# B172X.net
KiCad netlist of a schematic drawn in EAGLE
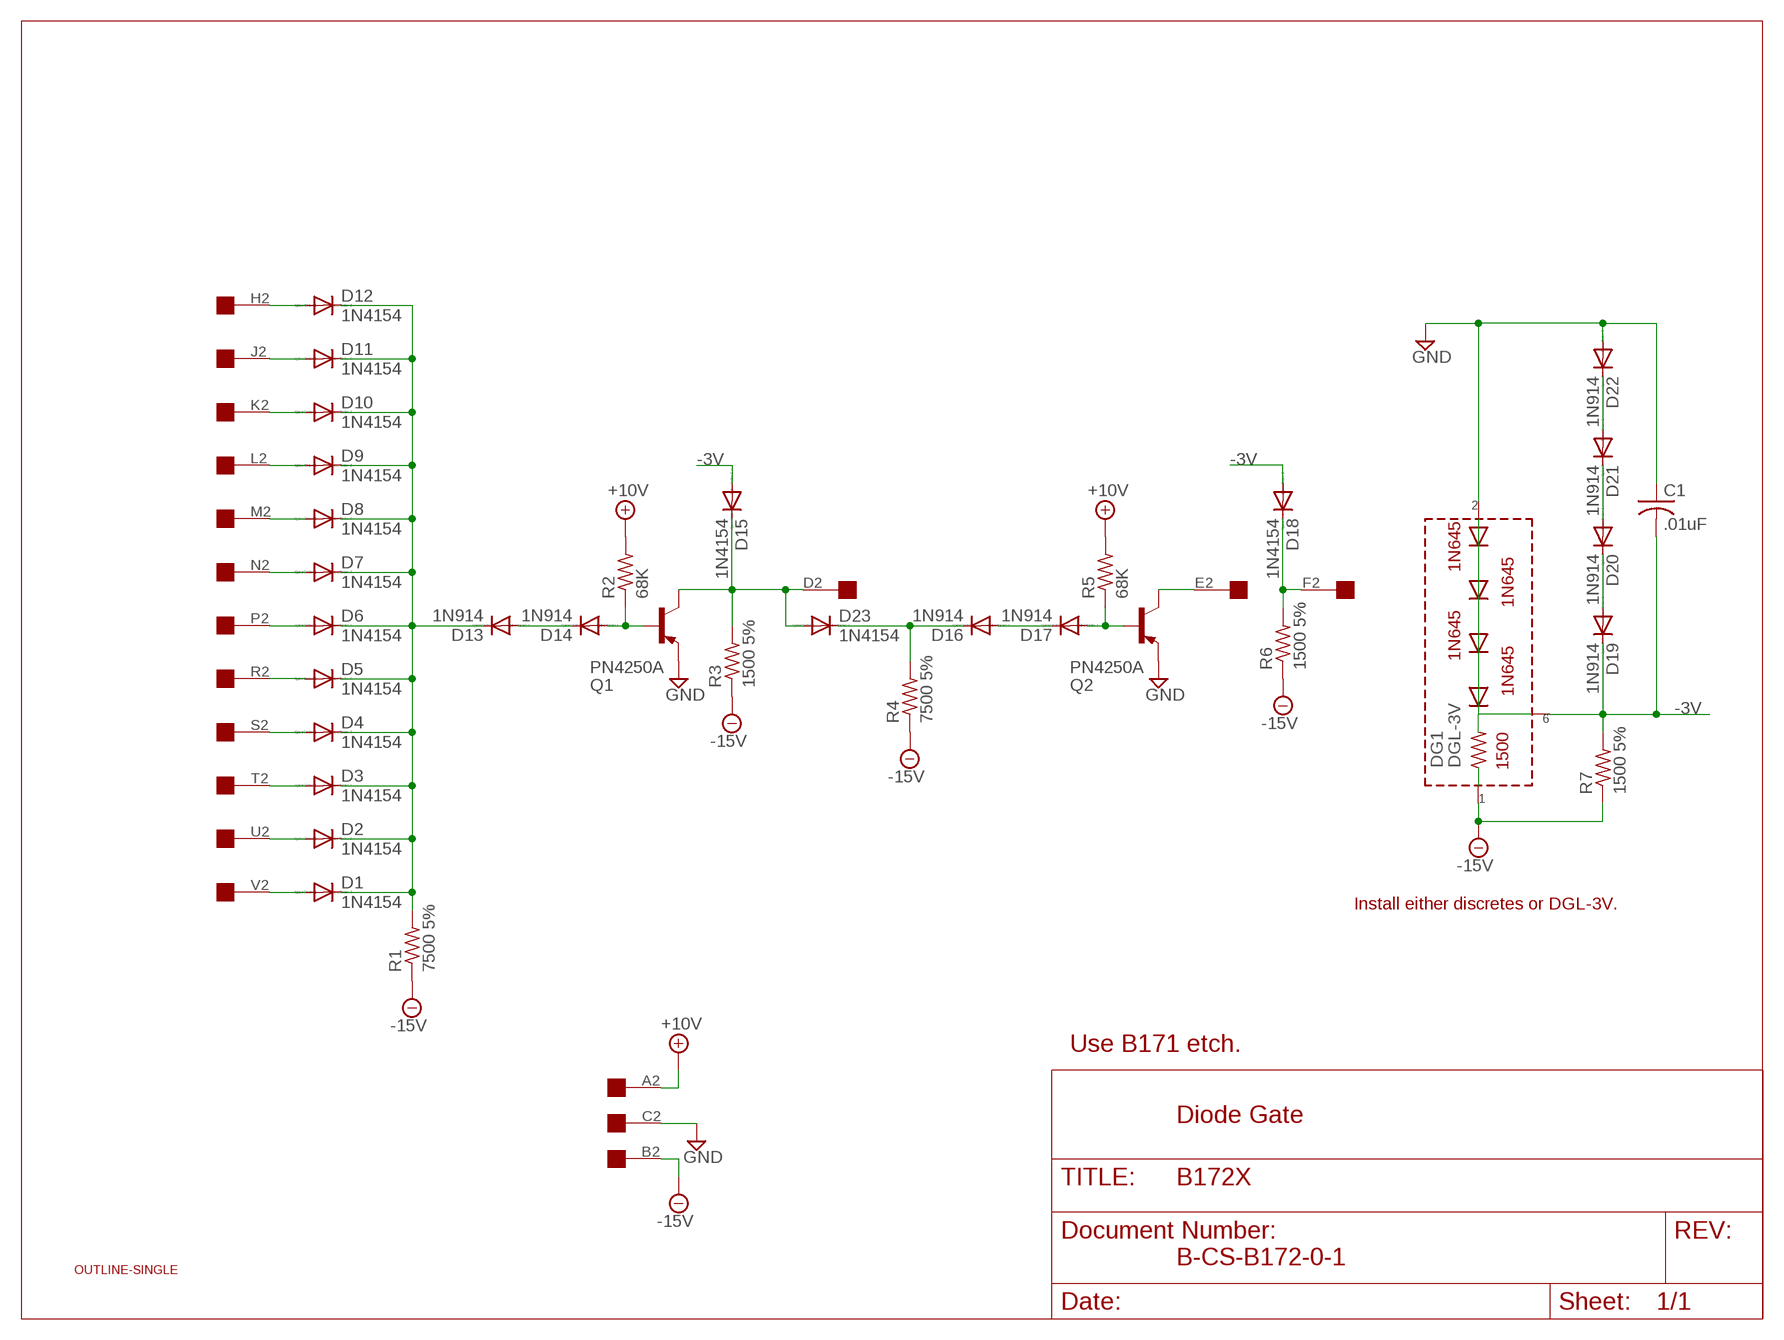
[diagram p0: schematic, sheet 1]

(export (version "E")
  (design (tool "Eeschema 10.0.6"))
  (components
    (comp (ref "C1")
      (value ".01uF")
      (footprint "eagle-import:C050-025X075")
      (libsource (lib "eagle-import") (part "C-US050-025X075"))
    )
    (comp (ref "D1")
      (value "1N4154")
      (footprint "eagle-import:DO35-10")
      (libsource (lib "eagle-import") (part "DIODE-DO35-10"))
    )
    (comp (ref "D2")
      (value "1N4154")
      (footprint "eagle-import:DO35-10")
      (libsource (lib "eagle-import") (part "DIODE-DO35-10"))
    )
    (comp (ref "D3")
      (value "1N4154")
      (footprint "eagle-import:DO35-10")
      (libsource (lib "eagle-import") (part "DIODE-DO35-10"))
    )
    (comp (ref "D4")
      (value "1N4154")
      (footprint "eagle-import:DO35-10")
      (libsource (lib "eagle-import") (part "DIODE-DO35-10"))
    )
    (comp (ref "D5")
      (value "1N4154")
      (footprint "eagle-import:DO35-10")
      (libsource (lib "eagle-import") (part "DIODE-DO35-10"))
    )
    (comp (ref "D6")
      (value "1N4154")
      (footprint "eagle-import:DO35-10")
      (libsource (lib "eagle-import") (part "DIODE-DO35-10"))
    )
    (comp (ref "D7")
      (value "1N4154")
      (footprint "eagle-import:DO35-10")
      (libsource (lib "eagle-import") (part "DIODE-DO35-10"))
    )
    (comp (ref "D8")
      (value "1N4154")
      (footprint "eagle-import:DO35-10")
      (libsource (lib "eagle-import") (part "DIODE-DO35-10"))
    )
    (comp (ref "D9")
      (value "1N4154")
      (footprint "eagle-import:DO35-10")
      (libsource (lib "eagle-import") (part "DIODE-DO35-10"))
    )
    (comp (ref "D10")
      (value "1N4154")
      (footprint "eagle-import:DO35-10")
      (libsource (lib "eagle-import") (part "DIODE-DO35-10"))
    )
    (comp (ref "D11")
      (value "1N4154")
      (footprint "eagle-import:DO35-10")
      (libsource (lib "eagle-import") (part "DIODE-DO35-10"))
    )
    (comp (ref "D12")
      (value "1N4154")
      (footprint "eagle-import:DO35-10")
      (libsource (lib "eagle-import") (part "DIODE-DO35-10"))
    )
    (comp (ref "D13")
      (value "1N914")
      (footprint "eagle-import:DO35-10")
      (libsource (lib "eagle-import") (part "DIODE-DO35-10"))
    )
    (comp (ref "D14")
      (value "1N914")
      (footprint "eagle-import:DO35-10")
      (libsource (lib "eagle-import") (part "DIODE-DO35-10"))
    )
    (comp (ref "D15")
      (value "1N4154")
      (footprint "eagle-import:DO35-10")
      (libsource (lib "eagle-import") (part "DIODE-DO35-10"))
    )
    (comp (ref "D16")
      (value "1N914")
      (footprint "eagle-import:DO35-10")
      (libsource (lib "eagle-import") (part "DIODE-DO35-10"))
    )
    (comp (ref "D17")
      (value "1N914")
      (footprint "eagle-import:DO35-10")
      (libsource (lib "eagle-import") (part "DIODE-DO35-10"))
    )
    (comp (ref "D18")
      (value "1N4154")
      (footprint "eagle-import:DO35-10")
      (libsource (lib "eagle-import") (part "DIODE-DO35-10"))
    )
    (comp (ref "D19")
      (value "1N914")
      (footprint "eagle-import:DO35-10")
      (libsource (lib "eagle-import") (part "DIODE-DO35-10"))
    )
    (comp (ref "D20")
      (value "1N914")
      (footprint "eagle-import:DO35-10")
      (libsource (lib "eagle-import") (part "DIODE-DO35-10"))
    )
    (comp (ref "D21")
      (value "1N914")
      (footprint "eagle-import:DO35-10")
      (libsource (lib "eagle-import") (part "DIODE-DO35-10"))
    )
    (comp (ref "D22")
      (value "1N914")
      (footprint "eagle-import:DO35-10")
      (libsource (lib "eagle-import") (part "DIODE-DO35-10"))
    )
    (comp (ref "D23")
      (value "1N4154")
      (footprint "eagle-import:DO35-10")
      (libsource (lib "eagle-import") (part "DIODE-DO35-10"))
    )
    (comp (ref "DG1")
      (value "DGL-3V")
      (footprint "eagle-import:DGL2")
      (libsource (lib "eagle-import") (part "DGL-3V"))
    )
    (comp (ref "Q1")
      (value "PN4250A")
      (footprint "eagle-import:TO5")
      (libsource (lib "eagle-import") (part "-PNP-TO5"))
    )
    (comp (ref "Q2")
      (value "PN4250A")
      (footprint "eagle-import:TO5")
      (libsource (lib "eagle-import") (part "-PNP-TO5"))
    )
    (comp (ref "R1")
      (value "7500 5%")
      (footprint "eagle-import:0207_10")
      (libsource (lib "eagle-import") (part "R-US_0207/10"))
    )
    (comp (ref "R2")
      (value "68K")
      (footprint "eagle-import:0207_10")
      (libsource (lib "eagle-import") (part "R-US_0207/10"))
    )
    (comp (ref "R3")
      (value "1500 5%")
      (footprint "eagle-import:0207_10")
      (libsource (lib "eagle-import") (part "R-US_0207/10"))
    )
    (comp (ref "R4")
      (value "7500 5%")
      (footprint "eagle-import:0207_10")
      (libsource (lib "eagle-import") (part "R-US_0207/10"))
    )
    (comp (ref "R5")
      (value "68K")
      (footprint "eagle-import:0207_10")
      (libsource (lib "eagle-import") (part "R-US_0207/10"))
    )
    (comp (ref "R6")
      (value "1500 5%")
      (footprint "eagle-import:0207_10")
      (libsource (lib "eagle-import") (part "R-US_0207/10"))
    )
    (comp (ref "R7")
      (value "1500 5%")
      (footprint "eagle-import:0207_10")
      (libsource (lib "eagle-import") (part "R-US_0207/10"))
    )
    (comp (ref "U$1")
      (value "OUTLINE-SINGLE")
      (footprint "eagle-import:SINGLE")
      (libsource (lib "eagle-import") (part "OUTLINE-SINGLE"))
    )
    (comp (ref "U$2")
      (value "EDGE-1")
      (footprint "eagle-import:EDGE-CON1")
      (libsource (lib "eagle-import") (part "EDGE-1"))
    )
  )
  (nets
    (net (code "1") (name "+10V") (class "Default")
      (node (ref "R2") (pin "2") (pinfunction "2_2") (pintype "passive"))
      (node (ref "R5") (pin "2") (pinfunction "2_2") (pintype "passive"))
      (node (ref "U$2") (pin "A2") (pinfunction "1_A2") (pintype "bidirectional"))
    )
    (net (code "2") (name "-15V") (class "Default")
      (node (ref "DG1") (pin "P$1") (pinfunction "1_P$1") (pintype "passive"))
      (node (ref "R1") (pin "1") (pinfunction "1_1") (pintype "passive"))
      (node (ref "R3") (pin "1") (pinfunction "1_1") (pintype "passive"))
      (node (ref "R4") (pin "1") (pinfunction "1_1") (pintype "passive"))
      (node (ref "R6") (pin "1") (pinfunction "1_1") (pintype "passive"))
      (node (ref "R7") (pin "1") (pinfunction "1_1") (pintype "passive"))
      (node (ref "U$2") (pin "B2") (pinfunction "1_B2") (pintype "bidirectional"))
    )
    (net (code "3") (name "/-3V") (class "Default")
      (node (ref "C1") (pin "2") (pinfunction "2_2") (pintype "passive"))
      (node (ref "D15") (pin "A") (pinfunction "A_A") (pintype "passive"))
      (node (ref "D18") (pin "A") (pinfunction "A_A") (pintype "passive"))
      (node (ref "D19") (pin "C") (pinfunction "C_C") (pintype "passive"))
      (node (ref "DG1") (pin "P$6") (pinfunction "6_P$6") (pintype "passive"))
      (node (ref "R7") (pin "2") (pinfunction "2_2") (pintype "passive"))
    )
    (net (code "4") (name "GND") (class "Default")
      (node (ref "C1") (pin "1") (pinfunction "1_1") (pintype "passive"))
      (node (ref "D22") (pin "A") (pinfunction "A_A") (pintype "passive"))
      (node (ref "DG1") (pin "P$2") (pinfunction "2_P$2") (pintype "passive"))
      (node (ref "Q1") (pin "1") (pinfunction "E_1") (pintype "passive"))
      (node (ref "Q2") (pin "1") (pinfunction "E_1") (pintype "passive"))
      (node (ref "U$2") (pin "C2") (pinfunction "1_C2") (pintype "bidirectional"))
    )
    (net (code "5") (name "Net-(D1-PadC)") (class "Default")
      (node (ref "D1") (pin "C") (pinfunction "C_C") (pintype "passive"))
      (node (ref "D10") (pin "C") (pinfunction "C_C") (pintype "passive"))
      (node (ref "D11") (pin "C") (pinfunction "C_C") (pintype "passive"))
      (node (ref "D12") (pin "C") (pinfunction "C_C") (pintype "passive"))
      (node (ref "D13") (pin "C") (pinfunction "C_C") (pintype "passive"))
      (node (ref "D2") (pin "C") (pinfunction "C_C") (pintype "passive"))
      (node (ref "D3") (pin "C") (pinfunction "C_C") (pintype "passive"))
      (node (ref "D4") (pin "C") (pinfunction "C_C") (pintype "passive"))
      (node (ref "D5") (pin "C") (pinfunction "C_C") (pintype "passive"))
      (node (ref "D6") (pin "C") (pinfunction "C_C") (pintype "passive"))
      (node (ref "D7") (pin "C") (pinfunction "C_C") (pintype "passive"))
      (node (ref "D8") (pin "C") (pinfunction "C_C") (pintype "passive"))
      (node (ref "D9") (pin "C") (pinfunction "C_C") (pintype "passive"))
      (node (ref "R1") (pin "2") (pinfunction "2_2") (pintype "passive"))
    )
    (net (code "6") (name "Net-(D13-PadA)") (class "Default")
      (node (ref "D13") (pin "A") (pinfunction "A_A") (pintype "passive"))
      (node (ref "D14") (pin "C") (pinfunction "C_C") (pintype "passive"))
    )
    (net (code "7") (name "Net-(D16-PadA)") (class "Default")
      (node (ref "D16") (pin "A") (pinfunction "A_A") (pintype "passive"))
      (node (ref "D17") (pin "C") (pinfunction "C_C") (pintype "passive"))
    )
    (net (code "8") (name "Net-(D16-PadC)") (class "Default")
      (node (ref "D16") (pin "C") (pinfunction "C_C") (pintype "passive"))
      (node (ref "D23") (pin "C") (pinfunction "C_C") (pintype "passive"))
      (node (ref "R4") (pin "2") (pinfunction "2_2") (pintype "passive"))
    )
    (net (code "9") (name "Net-(D19-PadA)") (class "Default")
      (node (ref "D19") (pin "A") (pinfunction "A_A") (pintype "passive"))
      (node (ref "D20") (pin "C") (pinfunction "C_C") (pintype "passive"))
    )
    (net (code "10") (name "Net-(D20-PadA)") (class "Default")
      (node (ref "D20") (pin "A") (pinfunction "A_A") (pintype "passive"))
      (node (ref "D21") (pin "C") (pinfunction "C_C") (pintype "passive"))
    )
    (net (code "11") (name "Net-(D21-PadA)") (class "Default")
      (node (ref "D21") (pin "A") (pinfunction "A_A") (pintype "passive"))
      (node (ref "D22") (pin "C") (pinfunction "C_C") (pintype "passive"))
    )
    (net (code "12") (name "Net-(Q1-B)") (class "Default")
      (node (ref "D14") (pin "A") (pinfunction "A_A") (pintype "passive"))
      (node (ref "Q1") (pin "2") (pinfunction "B_2") (pintype "passive"))
      (node (ref "R2") (pin "1") (pinfunction "1_1") (pintype "passive"))
    )
    (net (code "13") (name "Net-(Q1-C)") (class "Default")
      (node (ref "D15") (pin "C") (pinfunction "C_C") (pintype "passive"))
      (node (ref "D23") (pin "A") (pinfunction "A_A") (pintype "passive"))
      (node (ref "Q1") (pin "3") (pinfunction "C_3") (pintype "passive"))
      (node (ref "R3") (pin "2") (pinfunction "2_2") (pintype "passive"))
      (node (ref "U$2") (pin "D2") (pinfunction "1_D2") (pintype "bidirectional"))
    )
    (net (code "14") (name "Net-(Q2-B)") (class "Default")
      (node (ref "D17") (pin "A") (pinfunction "A_A") (pintype "passive"))
      (node (ref "Q2") (pin "2") (pinfunction "B_2") (pintype "passive"))
      (node (ref "R5") (pin "1") (pinfunction "1_1") (pintype "passive"))
    )
    (net (code "15") (name "Net-(Q2-C)") (class "Default")
      (node (ref "Q2") (pin "3") (pinfunction "C_3") (pintype "passive"))
      (node (ref "U$2") (pin "E2") (pinfunction "1_E2") (pintype "bidirectional"))
    )
    (net (code "16") (name "Net-(U$2F-1)") (class "Default")
      (node (ref "D18") (pin "C") (pinfunction "C_C") (pintype "passive"))
      (node (ref "R6") (pin "2") (pinfunction "2_2") (pintype "passive"))
      (node (ref "U$2") (pin "F2") (pinfunction "1_F2") (pintype "bidirectional"))
    )
    (net (code "17") (name "Net-(U$2G-1)") (class "Default")
      (node (ref "D12") (pin "A") (pinfunction "A_A") (pintype "passive"))
      (node (ref "U$2") (pin "H2") (pinfunction "1_H2") (pintype "bidirectional"))
    )
    (net (code "18") (name "Net-(U$2H-1)") (class "Default")
      (node (ref "D11") (pin "A") (pinfunction "A_A") (pintype "passive"))
      (node (ref "U$2") (pin "J2") (pinfunction "1_J2") (pintype "bidirectional"))
    )
    (net (code "19") (name "Net-(U$2I-1)") (class "Default")
      (node (ref "D10") (pin "A") (pinfunction "A_A") (pintype "passive"))
      (node (ref "U$2") (pin "K2") (pinfunction "1_K2") (pintype "bidirectional"))
    )
    (net (code "20") (name "Net-(U$2J-1)") (class "Default")
      (node (ref "D9") (pin "A") (pinfunction "A_A") (pintype "passive"))
      (node (ref "U$2") (pin "L2") (pinfunction "1_L2") (pintype "bidirectional"))
    )
    (net (code "21") (name "Net-(U$2K-1)") (class "Default")
      (node (ref "D8") (pin "A") (pinfunction "A_A") (pintype "passive"))
      (node (ref "U$2") (pin "M2") (pinfunction "1_M2") (pintype "bidirectional"))
    )
    (net (code "22") (name "Net-(U$2L-1)") (class "Default")
      (node (ref "D7") (pin "A") (pinfunction "A_A") (pintype "passive"))
      (node (ref "U$2") (pin "N2") (pinfunction "1_N2") (pintype "bidirectional"))
    )
    (net (code "23") (name "Net-(U$2M-1)") (class "Default")
      (node (ref "D6") (pin "A") (pinfunction "A_A") (pintype "passive"))
      (node (ref "U$2") (pin "P2") (pinfunction "1_P2") (pintype "bidirectional"))
    )
    (net (code "24") (name "Net-(U$2N-1)") (class "Default")
      (node (ref "D5") (pin "A") (pinfunction "A_A") (pintype "passive"))
      (node (ref "U$2") (pin "R2") (pinfunction "1_R2") (pintype "bidirectional"))
    )
    (net (code "25") (name "Net-(U$2O-1)") (class "Default")
      (node (ref "D4") (pin "A") (pinfunction "A_A") (pintype "passive"))
      (node (ref "U$2") (pin "S2") (pinfunction "1_S2") (pintype "bidirectional"))
    )
    (net (code "26") (name "Net-(U$2P-1)") (class "Default")
      (node (ref "D3") (pin "A") (pinfunction "A_A") (pintype "passive"))
      (node (ref "U$2") (pin "T2") (pinfunction "1_T2") (pintype "bidirectional"))
    )
    (net (code "27") (name "Net-(U$2Q-1)") (class "Default")
      (node (ref "D2") (pin "A") (pinfunction "A_A") (pintype "passive"))
      (node (ref "U$2") (pin "U2") (pinfunction "1_U2") (pintype "bidirectional"))
    )
    (net (code "28") (name "Net-(U$2R-1)") (class "Default")
      (node (ref "D1") (pin "A") (pinfunction "A_A") (pintype "passive"))
      (node (ref "U$2") (pin "V2") (pinfunction "1_V2") (pintype "bidirectional"))
    )
  )
)
